# Analog_Front_End.net
KiCad netlist of a schematic drawn in Altium Designer
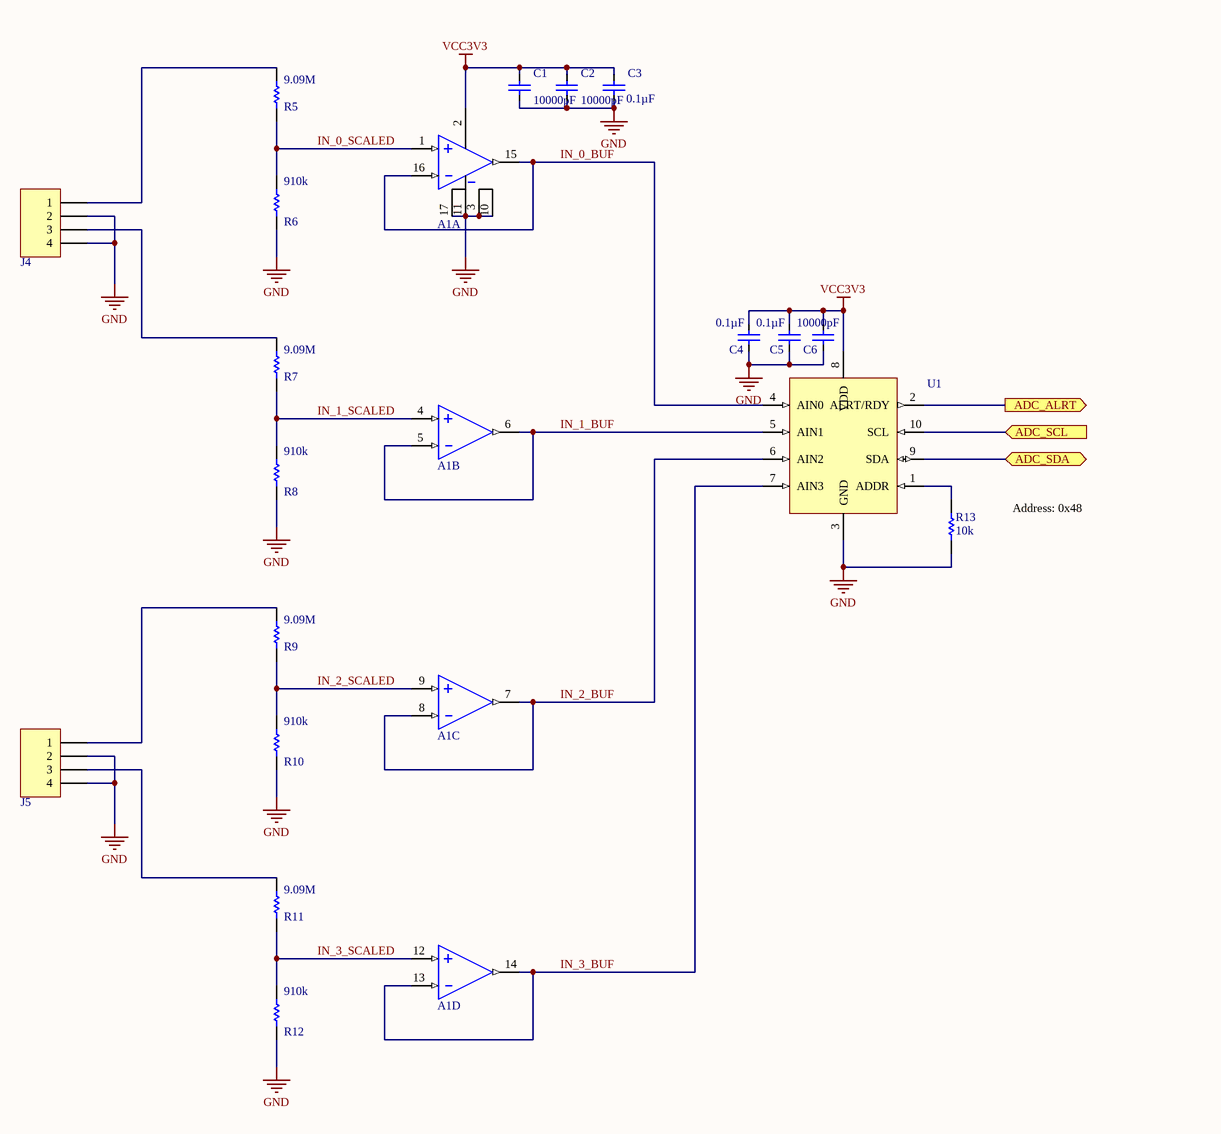
[diagram p0: Analog_Front_End.SchDoc]

(export (version "E")
  (design (tool "Eeschema 10.0.6"))
  (components
    (comp (ref "A1")
      (value "TSU104")
      (footprint "QFN50P300X300X100-17T180X180L")
      (description "IC OPAMP 5V CMOS NANOPWR 16QFN")
      (fields
        (field (name "MANUFACTURER") "STMicroelectronics")
        (field (name "MANUFACTURER PART NUMBER") "TSU104IQ4T")
      )
      (libsource (lib "mechanart_oshw") (part "TSU104"))
    )
    (comp (ref "C1")
      (value "10000pF")
      (footprint "CAPC1005X50L25N")
      (description "CAP CER 10000PF 50V X7R 0402")
      (fields
        (field (name "MANUFACTURER") "Murata Electronics North America")
        (field (name "MANUFACTURER PART NUMBER") "GRM155R71H103KA88D")
      )
      (libsource (lib "mechanart_oshw") (part "CapSMT"))
    )
    (comp (ref "C2")
      (value "10000pF")
      (footprint "CAPC1005X50L25N")
      (description "CAP CER 10000PF 50V X7R 0402")
      (fields
        (field (name "MANUFACTURER") "Murata Electronics North America")
        (field (name "MANUFACTURER PART NUMBER") "GRM155R71H103KA88D")
      )
      (libsource (lib "mechanart_oshw") (part "CapSMT"))
    )
    (comp (ref "C3")
      (value "0.1µF")
      (footprint "CAPC1005X50L25N")
      (description "CAP CER 0.1UF 50V X7R 0402")
      (fields
        (field (name "MANUFACTURER") "Murata Electronics North America")
        (field (name "MANUFACTURER PART NUMBER") "GRM155R71H104KE14D")
      )
      (libsource (lib "mechanart_oshw") (part "CapSMT"))
    )
    (comp (ref "C4")
      (value "0.1µF")
      (footprint "CAPC1005X50L25N")
      (description "CAP CER 0.1UF 50V X7R 0402")
      (fields
        (field (name "MANUFACTURER") "Murata Electronics North America")
        (field (name "MANUFACTURER PART NUMBER") "GRM155R71H104KE14D")
      )
      (libsource (lib "mechanart_oshw") (part "CapSMT"))
    )
    (comp (ref "C5")
      (value "0.1µF")
      (footprint "CAPC1005X50L25N")
      (description "CAP CER 0.1UF 50V X7R 0402")
      (fields
        (field (name "MANUFACTURER") "Murata Electronics North America")
        (field (name "MANUFACTURER PART NUMBER") "GRM155R71H104KE14D")
      )
      (libsource (lib "mechanart_oshw") (part "CapSMT"))
    )
    (comp (ref "C6")
      (value "10000pF")
      (footprint "CAPC1005X50L25N")
      (description "CAP CER 10000PF 50V X7R 0402")
      (fields
        (field (name "MANUFACTURER") "Murata Electronics North America")
        (field (name "MANUFACTURER PART NUMBER") "GRM155R71H103KA88D")
      )
      (libsource (lib "mechanart_oshw") (part "CapSMT"))
    )
    (comp (ref "J4")
      (value "~")
      (footprint "HEADER_4_RA")
      (description "CONN HEADER 4POS R/A GOLD T/H")
      (fields
        (field (name "MANUFACTURER") "TE Connectivity AMP Connectors")
        (field (name "MANUFACTURER PART NUMBER") "5-104186-1")
      )
      (libsource (lib "mechanart_oshw") (part "HEADER_4"))
    )
    (comp (ref "J5")
      (value "~")
      (footprint "HEADER_4_RA")
      (description "CONN HEADER 4POS R/A GOLD T/H")
      (fields
        (field (name "MANUFACTURER") "TE Connectivity AMP Connectors")
        (field (name "MANUFACTURER PART NUMBER") "5-104186-1")
      )
      (libsource (lib "mechanart_oshw") (part "HEADER_4"))
    )
    (comp (ref "R5")
      (value "9.09M")
      (footprint "RESC1508X50L30L")
      (description "RES SMD 9.09M OHM 1% 1/10W 0603")
      (fields
        (field (name "MANUFACTURER") "Vishay Dale")
        (field (name "MANUFACTURER PART NUMBER") "CRCW06039M09FKEA")
      )
      (libsource (lib "mechanart_oshw") (part "ResSMT"))
    )
    (comp (ref "R6")
      (value "910k")
      (footprint "RESC1508X50L30L")
      (description "RES SMD 910K OHM 1% 1/10W 0603")
      (fields
        (field (name "MANUFACTURER") "Vishay Dale")
        (field (name "MANUFACTURER PART NUMBER") "CRCW0603910KFKEA")
      )
      (libsource (lib "mechanart_oshw") (part "ResSMT"))
    )
    (comp (ref "R7")
      (value "9.09M")
      (footprint "RESC1508X50L30L")
      (description "RES SMD 9.09M OHM 1% 1/10W 0603")
      (fields
        (field (name "MANUFACTURER") "Vishay Dale")
        (field (name "MANUFACTURER PART NUMBER") "CRCW06039M09FKEA")
      )
      (libsource (lib "mechanart_oshw") (part "ResSMT"))
    )
    (comp (ref "R8")
      (value "910k")
      (footprint "RESC1508X50L30L")
      (description "RES SMD 910K OHM 1% 1/10W 0603")
      (fields
        (field (name "MANUFACTURER") "Vishay Dale")
        (field (name "MANUFACTURER PART NUMBER") "CRCW0603910KFKEA")
      )
      (libsource (lib "mechanart_oshw") (part "ResSMT"))
    )
    (comp (ref "R9")
      (value "9.09M")
      (footprint "RESC1508X50L30L")
      (description "RES SMD 9.09M OHM 1% 1/10W 0603")
      (fields
        (field (name "MANUFACTURER") "Vishay Dale")
        (field (name "MANUFACTURER PART NUMBER") "CRCW06039M09FKEA")
      )
      (libsource (lib "mechanart_oshw") (part "ResSMT"))
    )
    (comp (ref "R10")
      (value "910k")
      (footprint "RESC1508X50L30L")
      (description "RES SMD 910K OHM 1% 1/10W 0603")
      (fields
        (field (name "MANUFACTURER") "Vishay Dale")
        (field (name "MANUFACTURER PART NUMBER") "CRCW0603910KFKEA")
      )
      (libsource (lib "mechanart_oshw") (part "ResSMT"))
    )
    (comp (ref "R11")
      (value "9.09M")
      (footprint "RESC1508X50L30L")
      (description "RES SMD 9.09M OHM 1% 1/10W 0603")
      (fields
        (field (name "MANUFACTURER") "Vishay Dale")
        (field (name "MANUFACTURER PART NUMBER") "CRCW06039M09FKEA")
      )
      (libsource (lib "mechanart_oshw") (part "ResSMT"))
    )
    (comp (ref "R12")
      (value "910k")
      (footprint "RESC1508X50L30L")
      (description "RES SMD 910K OHM 1% 1/10W 0603")
      (fields
        (field (name "MANUFACTURER") "Vishay Dale")
        (field (name "MANUFACTURER PART NUMBER") "CRCW0603910KFKEA")
      )
      (libsource (lib "mechanart_oshw") (part "ResSMT"))
    )
    (comp (ref "R13")
      (value "10k")
      (footprint "RESC1005X40L25N")
      (description "RES SMD 10K OHM 5% 1/16W 0402")
      (fields
        (field (name "MANUFACTURER") "Vishay Dale")
        (field (name "MANUFACTURER PART NUMBER") "CRCW040210K0JNED")
      )
      (libsource (lib "mechanart_oshw") (part "ResSMT"))
    )
    (comp (ref "U1")
      (value "ADS1115")
      (footprint "X2QFN-10")
      (description "IC ADC 16-BIT I2C PROGBL 10-QFN")
      (fields
        (field (name "MANUFACTURER") "Texas Instruments")
        (field (name "MANUFACTURER PART NUMBER") "ADS1115IRUGT")
      )
      (libsource (lib "mechanart_oshw") (part "ADS1115"))
    )
  )
  (nets
    (net (code "1") (name "/ADC_ALRT") (class "Default")
      (node (ref "U1") (pin "2") (pinfunction "ALRT/RDY_2") (pintype "output"))
    )
    (net (code "2") (name "/ADC_SCL") (class "Default")
      (node (ref "U1") (pin "10") (pinfunction "SCL_10") (pintype "input"))
    )
    (net (code "3") (name "/ADC_SDA") (class "Default")
      (node (ref "U1") (pin "9") (pinfunction "SDA_9") (pintype "bidirectional"))
    )
    (net (code "4") (name "/IN_0_BUF") (class "Default")
      (node (ref "A1") (pin "15") (pinfunction "OUTA_15") (pintype "output"))
      (node (ref "A1") (pin "16") (pinfunction "INA_NEG_16") (pintype "input"))
      (node (ref "U1") (pin "4") (pinfunction "AIN0_4") (pintype "input"))
    )
    (net (code "5") (name "/IN_0_SCALED") (class "Default")
      (node (ref "A1") (pin "1") (pinfunction "INA_POS_1") (pintype "input"))
      (node (ref "R5") (pin "1") (pinfunction "1_1") (pintype "passive"))
      (node (ref "R6") (pin "2") (pinfunction "2_2") (pintype "passive"))
    )
    (net (code "6") (name "/IN_1_BUF") (class "Default")
      (node (ref "A1") (pin "5") (pinfunction "INB_NEG_5") (pintype "input"))
      (node (ref "A1") (pin "6") (pinfunction "OUTB_6") (pintype "output"))
      (node (ref "U1") (pin "5") (pinfunction "AIN1_5") (pintype "input"))
    )
    (net (code "7") (name "/IN_1_SCALED") (class "Default")
      (node (ref "A1") (pin "4") (pinfunction "INB_POS_4") (pintype "input"))
      (node (ref "R7") (pin "1") (pinfunction "1_1") (pintype "passive"))
      (node (ref "R8") (pin "2") (pinfunction "2_2") (pintype "passive"))
    )
    (net (code "8") (name "/IN_2_BUF") (class "Default")
      (node (ref "A1") (pin "7") (pinfunction "OUTC_7") (pintype "output"))
      (node (ref "A1") (pin "8") (pinfunction "INC_NEG_8") (pintype "input"))
      (node (ref "U1") (pin "6") (pinfunction "AIN2_6") (pintype "input"))
    )
    (net (code "9") (name "/IN_2_SCALED") (class "Default")
      (node (ref "A1") (pin "9") (pinfunction "INC_POS_9") (pintype "input"))
      (node (ref "R10") (pin "2") (pinfunction "2_2") (pintype "passive"))
      (node (ref "R9") (pin "1") (pinfunction "1_1") (pintype "passive"))
    )
    (net (code "10") (name "/IN_3_BUF") (class "Default")
      (node (ref "A1") (pin "13") (pinfunction "IND_NEG_13") (pintype "input"))
      (node (ref "A1") (pin "14") (pinfunction "OUTD_14") (pintype "output"))
      (node (ref "U1") (pin "7") (pinfunction "AIN3_7") (pintype "input"))
    )
    (net (code "11") (name "/IN_3_SCALED") (class "Default")
      (node (ref "A1") (pin "12") (pinfunction "IND_POS_12") (pintype "input"))
      (node (ref "R11") (pin "1") (pinfunction "1_1") (pintype "passive"))
      (node (ref "R12") (pin "2") (pinfunction "2_2") (pintype "passive"))
    )
    (net (code "12") (name "GND") (class "Default")
      (node (ref "A1") (pin "10") (pinfunction "NC_10") (pintype "passive"))
      (node (ref "A1") (pin "11") (pinfunction "VSS_11") (pintype "power_in"))
      (node (ref "A1") (pin "17") (pinfunction "PAD_17") (pintype "power_in"))
      (node (ref "A1") (pin "3") (pinfunction "NC_3") (pintype "passive"))
      (node (ref "C1") (pin "2") (pinfunction "2_2") (pintype "passive"))
      (node (ref "C2") (pin "2") (pinfunction "2_2") (pintype "passive"))
      (node (ref "C3") (pin "2") (pinfunction "2_2") (pintype "passive"))
      (node (ref "C4") (pin "2") (pinfunction "2_2") (pintype "passive"))
      (node (ref "C5") (pin "2") (pinfunction "2_2") (pintype "passive"))
      (node (ref "C6") (pin "2") (pinfunction "2_2") (pintype "passive"))
      (node (ref "J4") (pin "2") (pinfunction "2_2") (pintype "passive"))
      (node (ref "J4") (pin "4") (pinfunction "4_4") (pintype "passive"))
      (node (ref "J5") (pin "2") (pinfunction "2_2") (pintype "passive"))
      (node (ref "J5") (pin "4") (pinfunction "4_4") (pintype "passive"))
      (node (ref "R10") (pin "1") (pinfunction "1_1") (pintype "passive"))
      (node (ref "R12") (pin "1") (pinfunction "1_1") (pintype "passive"))
      (node (ref "R13") (pin "1") (pinfunction "1_1") (pintype "passive"))
      (node (ref "R6") (pin "1") (pinfunction "1_1") (pintype "passive"))
      (node (ref "R8") (pin "1") (pinfunction "1_1") (pintype "passive"))
      (node (ref "U1") (pin "3") (pinfunction "GND_3") (pintype "power_in"))
    )
    (net (code "13") (name "Net-(J4-Pad1)") (class "Default")
      (node (ref "J4") (pin "1") (pinfunction "1_1") (pintype "passive"))
      (node (ref "R5") (pin "2") (pinfunction "2_2") (pintype "passive"))
    )
    (net (code "14") (name "Net-(J4-Pad3)") (class "Default")
      (node (ref "J4") (pin "3") (pinfunction "3_3") (pintype "passive"))
      (node (ref "R7") (pin "2") (pinfunction "2_2") (pintype "passive"))
    )
    (net (code "15") (name "Net-(J5-Pad1)") (class "Default")
      (node (ref "J5") (pin "1") (pinfunction "1_1") (pintype "passive"))
      (node (ref "R9") (pin "2") (pinfunction "2_2") (pintype "passive"))
    )
    (net (code "16") (name "Net-(J5-Pad3)") (class "Default")
      (node (ref "J5") (pin "3") (pinfunction "3_3") (pintype "passive"))
      (node (ref "R11") (pin "2") (pinfunction "2_2") (pintype "passive"))
    )
    (net (code "17") (name "Net-(U1-ADDR)") (class "Default")
      (node (ref "R13") (pin "2") (pinfunction "2_2") (pintype "passive"))
      (node (ref "U1") (pin "1") (pinfunction "ADDR_1") (pintype "input"))
    )
    (net (code "18") (name "VCC3V3") (class "Default")
      (node (ref "A1") (pin "2") (pinfunction "VDD_2") (pintype "power_in"))
      (node (ref "C1") (pin "1") (pinfunction "1_1") (pintype "passive"))
      (node (ref "C2") (pin "1") (pinfunction "1_1") (pintype "passive"))
      (node (ref "C3") (pin "1") (pinfunction "1_1") (pintype "passive"))
      (node (ref "C4") (pin "1") (pinfunction "1_1") (pintype "passive"))
      (node (ref "C5") (pin "1") (pinfunction "1_1") (pintype "passive"))
      (node (ref "C6") (pin "1") (pinfunction "1_1") (pintype "passive"))
      (node (ref "U1") (pin "8") (pinfunction "VDD_8") (pintype "power_in"))
    )
  )
)
